# design.net
KiCad netlist of a schematic drawn in Altium Designer
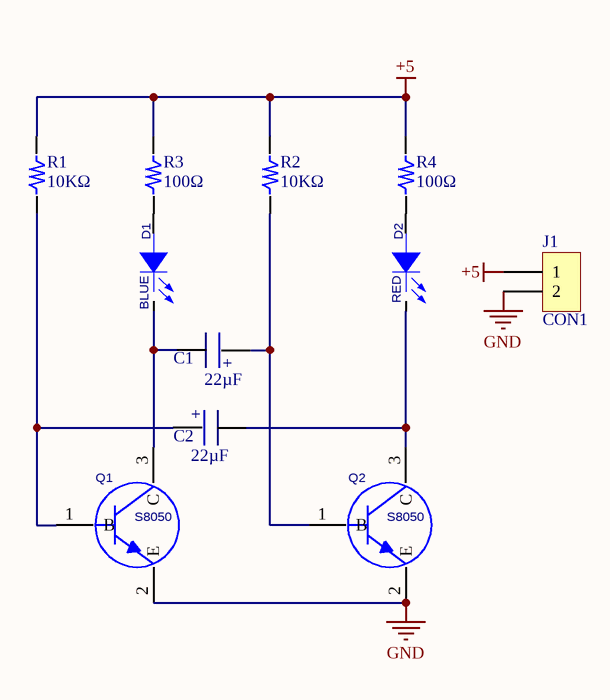
[diagram p0: 题目一原理图.SchDoc]

(export (version "E")
  (design (tool "Eeschema 10.0.6"))
  (components
    (comp (ref "C1") (value "22µF") (footprint "CAP_1") (libsource (lib "第一期AD元件库") (part "CAP+")))
    (comp (ref "C2") (value "22µF") (footprint "CAP_1") (libsource (lib "第一期AD元件库") (part "CAP+")))
    (comp (ref "D1")
      (value "BLUE")
      (footprint "LED_5MM")
      (fields (field (name "Comment") "LED"))
      (libsource (lib "第一期AD元件库") (part "LED"))
    )
    (comp (ref "D2")
      (value "RED")
      (footprint "LED_5MM")
      (fields (field (name "Comment") "LED"))
      (libsource (lib "第一期AD元件库") (part "LED"))
    )
    (comp (ref "J1")
      (value "CON1")
      (footprint "sip-2")
      (description "Connector")
      (libsource (lib "第一期AD元件库") (part "CON2"))
    )
    (comp (ref "Q1")
      (value "S8050")
      (footprint "TO-92")
      (description "NPN")
      (libsource (lib "第一期AD元件库") (part "S8050"))
    )
    (comp (ref "Q2")
      (value "S8050")
      (footprint "TO-92")
      (description "NPN")
      (libsource (lib "第一期AD元件库") (part "S8050"))
    )
    (comp (ref "R1") (value "10KΩ") (footprint "AXIAL0.4") (libsource (lib "第一期AD元件库") (part "RES")))
    (comp (ref "R2") (value "10KΩ") (footprint "AXIAL0.4") (libsource (lib "第一期AD元件库") (part "RES")))
    (comp (ref "R3") (value "100Ω") (footprint "AXIAL0.4") (libsource (lib "题目一考核") (part "RES")))
    (comp (ref "R4") (value "100Ω") (footprint "AXIAL0.4") (libsource (lib "题目一考核") (part "RES")))
  )
  (nets
    (net (code "1") (name "+5") (class "Default")
      (node (ref "J1") (pin "1") (pinfunction "1_1") (pintype "passive"))
      (node (ref "R1") (pin "2") (pinfunction "2_2") (pintype "passive"))
      (node (ref "R2") (pin "2") (pinfunction "2_2") (pintype "passive"))
      (node (ref "R3") (pin "2") (pinfunction "2_2") (pintype "passive"))
      (node (ref "R4") (pin "2") (pinfunction "2_2") (pintype "passive"))
    )
    (net (code "2") (name "GND") (class "Default")
      (node (ref "J1") (pin "2") (pinfunction "2_2") (pintype "passive"))
      (node (ref "Q1") (pin "2") (pinfunction "E_2") (pintype "passive"))
      (node (ref "Q2") (pin "2") (pinfunction "E_2") (pintype "passive"))
    )
    (net (code "3") (name "Net-(D1-ANODE)") (class "Default")
      (node (ref "D1") (pin "1") (pinfunction "ANODE_1") (pintype "passive"))
      (node (ref "R3") (pin "1") (pinfunction "1_1") (pintype "passive"))
    )
    (net (code "4") (name "Net-(D1-CATHODE)") (class "Default")
      (node (ref "C1") (pin "2") (pinfunction "2_2") (pintype "passive"))
      (node (ref "D1") (pin "2") (pinfunction "CATHODE_2") (pintype "passive"))
      (node (ref "Q1") (pin "3") (pinfunction "C_3") (pintype "passive"))
    )
    (net (code "5") (name "Net-(D2-ANODE)") (class "Default")
      (node (ref "D2") (pin "1") (pinfunction "ANODE_1") (pintype "passive"))
      (node (ref "R4") (pin "1") (pinfunction "1_1") (pintype "passive"))
    )
    (net (code "6") (name "Net-(D2-CATHODE)") (class "Default")
      (node (ref "C2") (pin "2") (pinfunction "2_2") (pintype "passive"))
      (node (ref "D2") (pin "2") (pinfunction "CATHODE_2") (pintype "passive"))
      (node (ref "Q2") (pin "3") (pinfunction "C_3") (pintype "passive"))
    )
    (net (code "7") (name "Net-(Q1-B)") (class "Default")
      (node (ref "C2") (pin "1") (pinfunction "1_1") (pintype "passive"))
      (node (ref "Q1") (pin "1") (pinfunction "B_1") (pintype "passive"))
      (node (ref "R1") (pin "1") (pinfunction "1_1") (pintype "passive"))
    )
    (net (code "8") (name "Net-(Q2-B)") (class "Default")
      (node (ref "C1") (pin "1") (pinfunction "1_1") (pintype "passive"))
      (node (ref "Q2") (pin "1") (pinfunction "B_1") (pintype "passive"))
      (node (ref "R2") (pin "1") (pinfunction "1_1") (pintype "passive"))
    )
  )
)
